# Pg1_Top_Sheet_and_Micro.net
KiCad netlist of a schematic drawn in Altium Designer
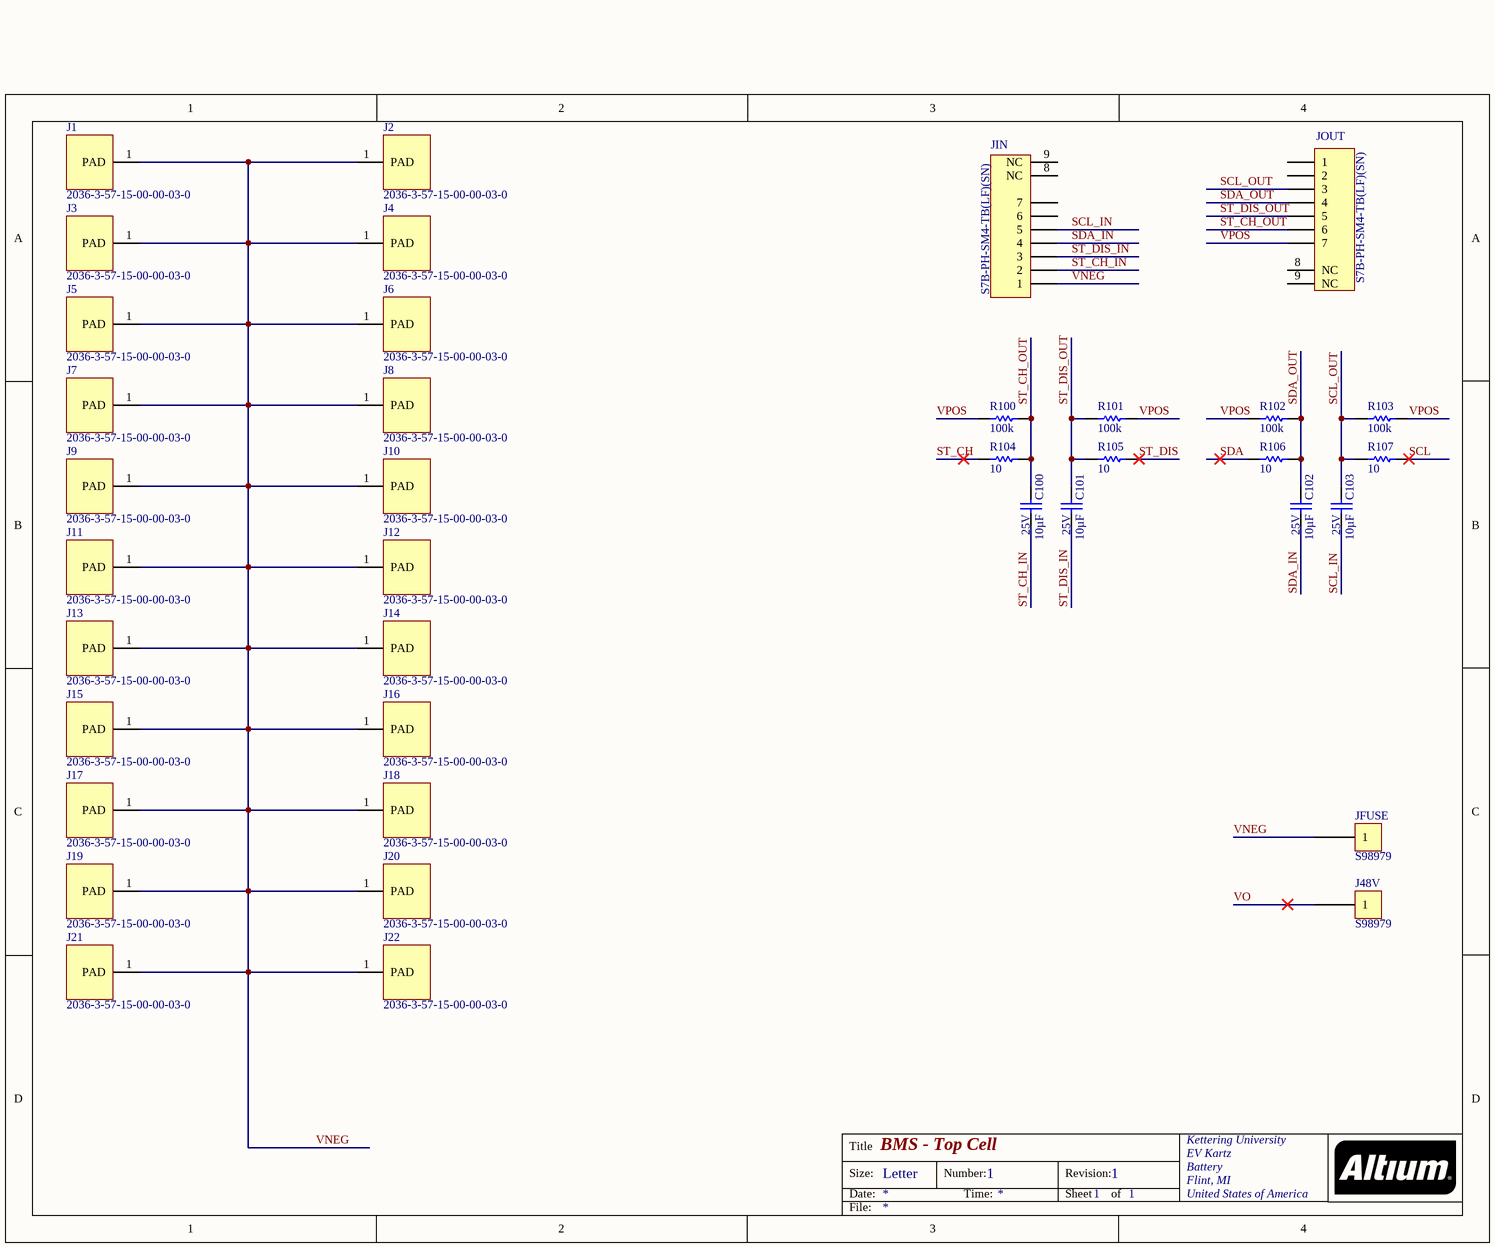
[diagram p0: Pg1 Top Sheet and Micro.SchDoc]

(export (version "E")
  (design (tool "Eeschema 10.0.6"))
  (components
    (comp (ref "C100")
      (value "10µF")
      (footprint "CAPC3225N")
      (description "Capacitor, Ceramic, 10µF, 25V, 0805, 10%, 125C")
      (fields (field (name "RATED") "25V") (field (name "Comment") "C1210C106K3RACAUTO"))
      (libsource (lib "SchLib - EE391 Master") (part "C1210C106K3RACAUTO"))
    )
    (comp (ref "C101")
      (value "10µF")
      (footprint "CAPC3225N")
      (description "Capacitor, Ceramic, 10µF, 25V, 0805, 10%, 125C")
      (fields (field (name "RATED") "25V") (field (name "Comment") "C1210C106K3RACAUTO"))
      (libsource (lib "SchLib - EE391 Master") (part "C1210C106K3RACAUTO"))
    )
    (comp (ref "C102")
      (value "10µF")
      (footprint "CAPC3225N")
      (description "Capacitor, Ceramic, 10µF, 25V, 0805, 10%, 125C")
      (fields (field (name "RATED") "25V") (field (name "Comment") "C1210C106K3RACAUTO"))
      (libsource (lib "SchLib - EE391 Master") (part "C1210C106K3RACAUTO"))
    )
    (comp (ref "C103")
      (value "10µF")
      (footprint "CAPC3225N")
      (description "Capacitor, Ceramic, 10µF, 25V, 0805, 10%, 125C")
      (fields (field (name "RATED") "25V") (field (name "Comment") "C1210C106K3RACAUTO"))
      (libsource (lib "SchLib - EE391 Master") (part "C1210C106K3RACAUTO"))
    )
    (comp (ref "J1")
      (value "2036-3-57-15-00-00-03-0")
      (footprint "6mm Pad")
      (description "Hardware, Sprint Contact Surface")
      (libsource (lib "") (part "2036-3-57-15-00-00-03-0_1"))
    )
    (comp (ref "J2")
      (value "2036-3-57-15-00-00-03-0")
      (footprint "6mm Pad")
      (description "Hardware, Sprint Contact Surface")
      (libsource (lib "SchLib - EE391 Master") (part "2036-3-57-15-00-00-03-0"))
    )
    (comp (ref "J3")
      (value "2036-3-57-15-00-00-03-0")
      (footprint "6mm Pad")
      (description "Hardware, Sprint Contact Surface")
      (libsource (lib "") (part "2036-3-57-15-00-00-03-0_1"))
    )
    (comp (ref "J4")
      (value "2036-3-57-15-00-00-03-0")
      (footprint "6mm Pad")
      (description "Hardware, Sprint Contact Surface")
      (libsource (lib "SchLib - EE391 Master") (part "2036-3-57-15-00-00-03-0"))
    )
    (comp (ref "J5")
      (value "2036-3-57-15-00-00-03-0")
      (footprint "6mm Pad")
      (description "Hardware, Sprint Contact Surface")
      (libsource (lib "") (part "2036-3-57-15-00-00-03-0_1"))
    )
    (comp (ref "J6")
      (value "2036-3-57-15-00-00-03-0")
      (footprint "6mm Pad")
      (description "Hardware, Sprint Contact Surface")
      (libsource (lib "SchLib - EE391 Master") (part "2036-3-57-15-00-00-03-0"))
    )
    (comp (ref "J7")
      (value "2036-3-57-15-00-00-03-0")
      (footprint "6mm Pad")
      (description "Hardware, Sprint Contact Surface")
      (libsource (lib "") (part "2036-3-57-15-00-00-03-0_1"))
    )
    (comp (ref "J8")
      (value "2036-3-57-15-00-00-03-0")
      (footprint "6mm Pad")
      (description "Hardware, Sprint Contact Surface")
      (libsource (lib "SchLib - EE391 Master") (part "2036-3-57-15-00-00-03-0"))
    )
    (comp (ref "J9")
      (value "2036-3-57-15-00-00-03-0")
      (footprint "6mm Pad")
      (description "Hardware, Sprint Contact Surface")
      (libsource (lib "") (part "2036-3-57-15-00-00-03-0_1"))
    )
    (comp (ref "J10")
      (value "2036-3-57-15-00-00-03-0")
      (footprint "6mm Pad")
      (description "Hardware, Sprint Contact Surface")
      (libsource (lib "SchLib - EE391 Master") (part "2036-3-57-15-00-00-03-0"))
    )
    (comp (ref "J11")
      (value "2036-3-57-15-00-00-03-0")
      (footprint "6mm Pad")
      (description "Hardware, Sprint Contact Surface")
      (libsource (lib "") (part "2036-3-57-15-00-00-03-0_1"))
    )
    (comp (ref "J12")
      (value "2036-3-57-15-00-00-03-0")
      (footprint "6mm Pad")
      (description "Hardware, Sprint Contact Surface")
      (libsource (lib "SchLib - EE391 Master") (part "2036-3-57-15-00-00-03-0"))
    )
    (comp (ref "J13")
      (value "2036-3-57-15-00-00-03-0")
      (footprint "6mm Pad")
      (description "Hardware, Sprint Contact Surface")
      (libsource (lib "") (part "2036-3-57-15-00-00-03-0_1"))
    )
    (comp (ref "J14")
      (value "2036-3-57-15-00-00-03-0")
      (footprint "6mm Pad")
      (description "Hardware, Sprint Contact Surface")
      (libsource (lib "SchLib - EE391 Master") (part "2036-3-57-15-00-00-03-0"))
    )
    (comp (ref "J15")
      (value "2036-3-57-15-00-00-03-0")
      (footprint "6mm Pad")
      (description "Hardware, Sprint Contact Surface")
      (libsource (lib "") (part "2036-3-57-15-00-00-03-0_1"))
    )
    (comp (ref "J16")
      (value "2036-3-57-15-00-00-03-0")
      (footprint "6mm Pad")
      (description "Hardware, Sprint Contact Surface")
      (libsource (lib "SchLib - EE391 Master") (part "2036-3-57-15-00-00-03-0"))
    )
    (comp (ref "J17")
      (value "2036-3-57-15-00-00-03-0")
      (footprint "6mm Pad")
      (description "Hardware, Sprint Contact Surface")
      (libsource (lib "") (part "2036-3-57-15-00-00-03-0_1"))
    )
    (comp (ref "J18")
      (value "2036-3-57-15-00-00-03-0")
      (footprint "6mm Pad")
      (description "Hardware, Sprint Contact Surface")
      (libsource (lib "SchLib - EE391 Master") (part "2036-3-57-15-00-00-03-0"))
    )
    (comp (ref "J19")
      (value "2036-3-57-15-00-00-03-0")
      (footprint "6mm Pad")
      (description "Hardware, Sprint Contact Surface")
      (libsource (lib "") (part "2036-3-57-15-00-00-03-0_1"))
    )
    (comp (ref "J20")
      (value "2036-3-57-15-00-00-03-0")
      (footprint "6mm Pad")
      (description "Hardware, Sprint Contact Surface")
      (libsource (lib "SchLib - EE391 Master") (part "2036-3-57-15-00-00-03-0"))
    )
    (comp (ref "J21")
      (value "2036-3-57-15-00-00-03-0")
      (footprint "6mm Pad")
      (description "Hardware, Sprint Contact Surface")
      (libsource (lib "") (part "2036-3-57-15-00-00-03-0_1"))
    )
    (comp (ref "J22")
      (value "2036-3-57-15-00-00-03-0")
      (footprint "6mm Pad")
      (description "Hardware, Sprint Contact Surface")
      (libsource (lib "SchLib - EE391 Master") (part "2036-3-57-15-00-00-03-0"))
    )
    (comp (ref "J48V")
      (value "S98979")
      (footprint "S98979")
      (description "Screw Terminal M8, 360A")
      (libsource (lib "Connectors") (part "S98979"))
    )
    (comp (ref "JFUSE")
      (value "S98979")
      (footprint "S98979")
      (description "Screw Terminal M8, 360A")
      (libsource (lib "Connectors") (part "S98979"))
    )
    (comp (ref "JIN")
      (value "S7B-PH-SM4-TB(LF)(SN)")
      (footprint "JST-PH-S7")
      (description "Header, JST, 7-Pin, Right-Angle, PH, Surface Mount")
      (libsource (lib "SchLib - EE391 Master") (part "S7B-PH-SM4-TB(LF)(SN)"))
    )
    (comp (ref "JOUT")
      (value "S7B-PH-SM4-TB(LF)(SN)")
      (footprint "JST-PH-S7")
      (description "Header, JST, 7-Pin, Right-Angle, PH, Surface Mount")
      (libsource (lib "") (part "S7B-PH-SM4-TB(LF)(SN)_1"))
    )
    (comp (ref "R100")
      (value "100k")
      (footprint "RESC2012N")
      (description "Resistor, Fixed, 100 kOhm, 0805, 1%, 1/8W")
      (fields (field (name "Comment") "ERJ-6ENF1003V"))
      (libsource (lib "SchLib - EE391 Master") (part "ERJ-6ENF1003V"))
    )
    (comp (ref "R101")
      (value "100k")
      (footprint "RESC2012N")
      (description "Resistor, Fixed, 100 kOhm, 0805, 1%, 1/8W")
      (fields (field (name "Comment") "ERJ-6ENF1003V"))
      (libsource (lib "SchLib - EE391 Master") (part "ERJ-6ENF1003V"))
    )
    (comp (ref "R102")
      (value "100k")
      (footprint "RESC2012N")
      (description "Resistor, Fixed, 100 kOhm, 0805, 1%, 1/8W")
      (fields (field (name "Comment") "ERJ-6ENF1003V"))
      (libsource (lib "SchLib - EE391 Master") (part "ERJ-6ENF1003V"))
    )
    (comp (ref "R103")
      (value "100k")
      (footprint "RESC2012N")
      (description "Resistor, Fixed, 100 kOhm, 0805, 1%, 1/8W")
      (fields (field (name "Comment") "ERJ-6ENF1003V"))
      (libsource (lib "SchLib - EE391 Master") (part "ERJ-6ENF1003V"))
    )
    (comp (ref "R104")
      (value "10")
      (footprint "RESC2012N")
      (description "Resistor, Fixed, 10 Ohm, 0805, 1%, 1/8W")
      (fields (field (name "Comment") "ERJ-6ENF10R0V"))
      (libsource (lib "SchLib - EE391 Master") (part "ERJ-6ENF10R0V"))
    )
    (comp (ref "R105")
      (value "10")
      (footprint "RESC2012N")
      (description "Resistor, Fixed, 10 Ohm, 0805, 1%, 1/8W")
      (fields (field (name "Comment") "ERJ-6ENF10R0V"))
      (libsource (lib "SchLib - EE391 Master") (part "ERJ-6ENF10R0V"))
    )
    (comp (ref "R106")
      (value "10")
      (footprint "RESC2012N")
      (description "Resistor, Fixed, 10 Ohm, 0805, 1%, 1/8W")
      (fields (field (name "Comment") "ERJ-6ENF10R0V"))
      (libsource (lib "SchLib - EE391 Master") (part "ERJ-6ENF10R0V"))
    )
    (comp (ref "R107")
      (value "10")
      (footprint "RESC2012N")
      (description "Resistor, Fixed, 10 Ohm, 0805, 1%, 1/8W")
      (fields (field (name "Comment") "ERJ-6ENF10R0V"))
      (libsource (lib "SchLib - EE391 Master") (part "ERJ-6ENF10R0V"))
    )
  )
  (nets
    (net (code "1") (name "/SCL") (class "Default")
      (node (ref "R107") (pin "2") (pinfunction "2_2") (pintype "passive+no_connect"))
    )
    (net (code "2") (name "/SCL_IN") (class "Default")
      (node (ref "C103") (pin "1") (pinfunction "1_1") (pintype "passive"))
      (node (ref "JIN") (pin "5") (pinfunction "5_5") (pintype "passive"))
    )
    (net (code "3") (name "/SCL_OUT") (class "Default")
      (node (ref "C103") (pin "2") (pinfunction "2_2") (pintype "passive"))
      (node (ref "JOUT") (pin "3") (pinfunction "3_3") (pintype "passive"))
      (node (ref "R103") (pin "2") (pinfunction "2_2") (pintype "passive"))
      (node (ref "R107") (pin "1") (pinfunction "1_1") (pintype "passive"))
    )
    (net (code "5") (name "/SDA") (class "Default")
      (node (ref "R106") (pin "1") (pinfunction "1_1") (pintype "passive"))
    )
    (net (code "6") (name "/SDA_IN") (class "Default")
      (node (ref "C102") (pin "1") (pinfunction "1_1") (pintype "passive"))
      (node (ref "JIN") (pin "4") (pinfunction "4_4") (pintype "passive"))
    )
    (net (code "7") (name "/SDA_OUT") (class "Default")
      (node (ref "C102") (pin "2") (pinfunction "2_2") (pintype "passive"))
      (node (ref "JOUT") (pin "4") (pinfunction "4_4") (pintype "passive"))
      (node (ref "R102") (pin "1") (pinfunction "1_1") (pintype "passive"))
      (node (ref "R106") (pin "2") (pinfunction "2_2") (pintype "passive"))
    )
    (net (code "8") (name "/ST_CH") (class "Default")
      (node (ref "R104") (pin "1") (pinfunction "1_1") (pintype "passive"))
    )
    (net (code "9") (name "/ST_CH_IN") (class "Default")
      (node (ref "C100") (pin "1") (pinfunction "1_1") (pintype "passive"))
      (node (ref "JIN") (pin "2") (pinfunction "2_2") (pintype "passive"))
    )
    (net (code "10") (name "/ST_CH_OUT") (class "Default")
      (node (ref "C100") (pin "2") (pinfunction "2_2") (pintype "passive"))
      (node (ref "JOUT") (pin "6") (pinfunction "6_6") (pintype "passive"))
      (node (ref "R100") (pin "1") (pinfunction "1_1") (pintype "passive"))
      (node (ref "R104") (pin "2") (pinfunction "2_2") (pintype "passive"))
    )
    (net (code "11") (name "/ST_DIS") (class "Default")
      (node (ref "R105") (pin "2") (pinfunction "2_2") (pintype "passive+no_connect"))
    )
    (net (code "12") (name "/ST_DIS_IN") (class "Default")
      (node (ref "C101") (pin "1") (pinfunction "1_1") (pintype "passive"))
      (node (ref "JIN") (pin "3") (pinfunction "3_3") (pintype "passive"))
    )
    (net (code "13") (name "/ST_DIS_OUT") (class "Default")
      (node (ref "C101") (pin "2") (pinfunction "2_2") (pintype "passive"))
      (node (ref "JOUT") (pin "5") (pinfunction "5_5") (pintype "passive"))
      (node (ref "R101") (pin "2") (pinfunction "2_2") (pintype "passive"))
      (node (ref "R105") (pin "1") (pinfunction "1_1") (pintype "passive"))
    )
    (net (code "14") (name "/VNEG") (class "Default")
      (node (ref "J1") (pin "1") (pinfunction "PAD_1") (pintype "passive"))
      (node (ref "J10") (pin "1") (pinfunction "PAD_1") (pintype "passive"))
      (node (ref "J11") (pin "1") (pinfunction "PAD_1") (pintype "passive"))
      (node (ref "J12") (pin "1") (pinfunction "PAD_1") (pintype "passive"))
      (node (ref "J13") (pin "1") (pinfunction "PAD_1") (pintype "passive"))
      (node (ref "J14") (pin "1") (pinfunction "PAD_1") (pintype "passive"))
      (node (ref "J15") (pin "1") (pinfunction "PAD_1") (pintype "passive"))
      (node (ref "J16") (pin "1") (pinfunction "PAD_1") (pintype "passive"))
      (node (ref "J17") (pin "1") (pinfunction "PAD_1") (pintype "passive"))
      (node (ref "J18") (pin "1") (pinfunction "PAD_1") (pintype "passive"))
      (node (ref "J19") (pin "1") (pinfunction "PAD_1") (pintype "passive"))
      (node (ref "J2") (pin "1") (pinfunction "PAD_1") (pintype "passive"))
      (node (ref "J20") (pin "1") (pinfunction "PAD_1") (pintype "passive"))
      (node (ref "J21") (pin "1") (pinfunction "PAD_1") (pintype "passive"))
      (node (ref "J22") (pin "1") (pinfunction "PAD_1") (pintype "passive"))
      (node (ref "J3") (pin "1") (pinfunction "PAD_1") (pintype "passive"))
      (node (ref "J4") (pin "1") (pinfunction "PAD_1") (pintype "passive"))
      (node (ref "J5") (pin "1") (pinfunction "PAD_1") (pintype "passive"))
      (node (ref "J6") (pin "1") (pinfunction "PAD_1") (pintype "passive"))
      (node (ref "J7") (pin "1") (pinfunction "PAD_1") (pintype "passive"))
      (node (ref "J8") (pin "1") (pinfunction "PAD_1") (pintype "passive"))
      (node (ref "J9") (pin "1") (pinfunction "PAD_1") (pintype "passive"))
      (node (ref "JFUSE") (pin "1") (pinfunction "1_1") (pintype "passive"))
      (node (ref "JIN") (pin "1") (pinfunction "1_1") (pintype "passive"))
    )
    (net (code "15") (name "/VO") (class "Default")
      (node (ref "J48V") (pin "1") (pinfunction "1_1") (pintype "passive"))
    )
    (net (code "16") (name "/VPOS") (class "Default")
      (node (ref "JOUT") (pin "7") (pinfunction "7_7") (pintype "passive"))
      (node (ref "R100") (pin "2") (pinfunction "2_2") (pintype "passive"))
      (node (ref "R101") (pin "1") (pinfunction "1_1") (pintype "passive"))
      (node (ref "R102") (pin "2") (pinfunction "2_2") (pintype "passive"))
      (node (ref "R103") (pin "1") (pinfunction "1_1") (pintype "passive"))
    )
    (net (code "17") (name "unconnected-(JIN-NC-Pad8)") (class "Default")
      (node (ref "JIN") (pin "8") (pinfunction "NC_8") (pintype "tri_state"))
    )
    (net (code "18") (name "unconnected-(JIN-NC-Pad9)") (class "Default")
      (node (ref "JIN") (pin "9") (pinfunction "NC_9") (pintype "tri_state"))
    )
    (net (code "19") (name "unconnected-(JIN-Pad6)") (class "Default")
      (node (ref "JIN") (pin "6") (pinfunction "6_6") (pintype "passive"))
    )
    (net (code "20") (name "unconnected-(JIN-Pad7)") (class "Default")
      (node (ref "JIN") (pin "7") (pinfunction "7_7") (pintype "passive"))
    )
    (net (code "21") (name "unconnected-(JOUT-NC-Pad8)") (class "Default")
      (node (ref "JOUT") (pin "8") (pinfunction "NC_8") (pintype "tri_state"))
    )
    (net (code "22") (name "unconnected-(JOUT-NC-Pad9)") (class "Default")
      (node (ref "JOUT") (pin "9") (pinfunction "NC_9") (pintype "tri_state"))
    )
    (net (code "23") (name "unconnected-(JOUT-Pad1)") (class "Default")
      (node (ref "JOUT") (pin "1") (pinfunction "1_1") (pintype "passive"))
    )
    (net (code "24") (name "unconnected-(JOUT-Pad2)") (class "Default")
      (node (ref "JOUT") (pin "2") (pinfunction "2_2") (pintype "passive"))
    )
  )
)
